# Battery_Charger.net
KiCad netlist of a schematic drawn in Altium Designer
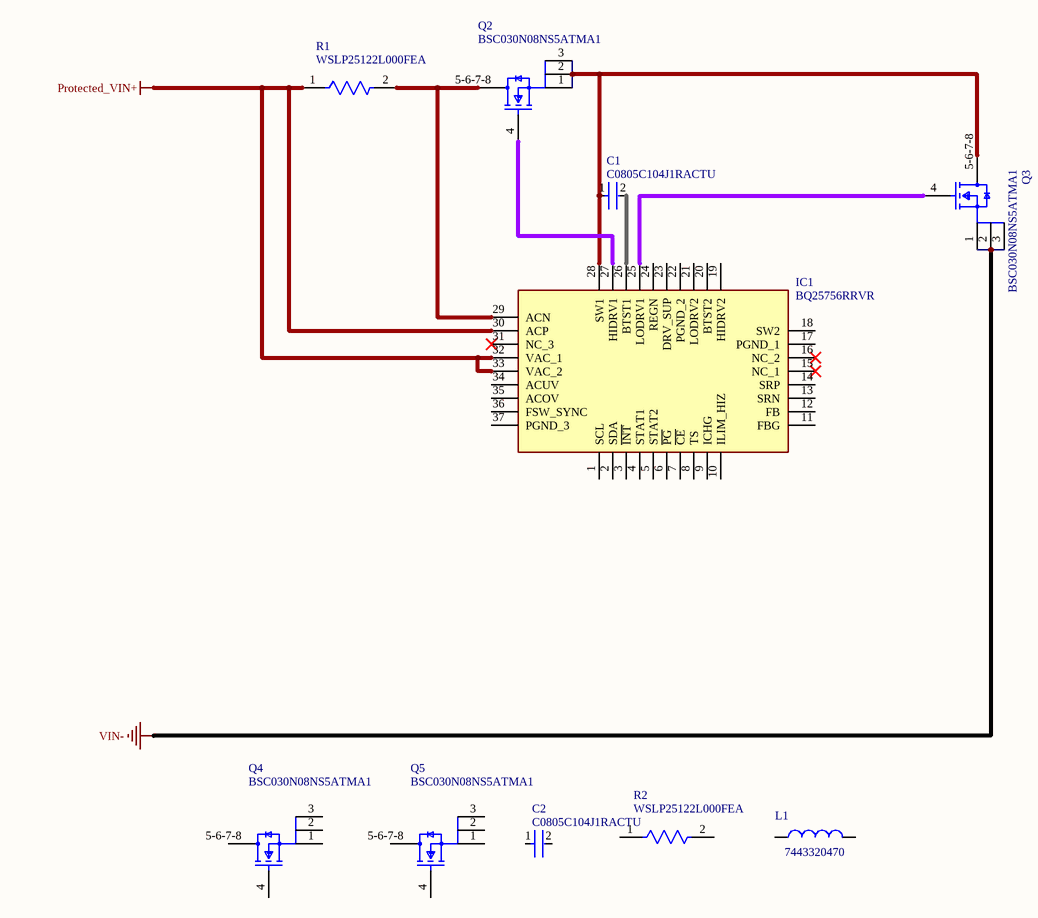
[diagram p0: Battery_Charger.SchDoc]

(export (version "E")
  (design (tool "Eeschema 10.0.6"))
  (components
    (comp (ref "C1")
      (value "C0805C104J1RACTU")
      (footprint "FP-C0805C-DN-MFG")
      (description "CAP CER 0.1UF 100V 5% X7R 0805")
      (fields
        (field (name "OCTOPART") "https://octopart.com/c0805c104j1ractu-kemet-10469001")
        (field (name "MANUFACTURER") "KEMET")
      )
      (libsource (lib "Altium Content Vault") (part "b4654b650e69147ec39a6b967a45e02"))
    )
    (comp (ref "C2")
      (value "C0805C104J1RACTU")
      (footprint "FP-C0805C-DN-MFG")
      (description "CAP CER 0.1UF 100V 5% X7R 0805")
      (fields
        (field (name "OCTOPART") "https://octopart.com/c0805c104j1ractu-kemet-10469001")
        (field (name "MANUFACTURER") "KEMET")
      )
      (libsource (lib "Altium Content Vault") (part "b4654b650e69147ec39a6b967a45e02"))
    )
    (comp (ref "IC1")
      (value "BQ25756RRVR")
      (footprint "BQ25756RRVR:QFN50P500X600X100-37N-D")
      (description "Integrated Circuit")
      (fields (field (name "MOUSER PART NUMBER") "595-BQ25756RRVR"))
      (libsource (lib "BQ25756RRVR") (part "BQ25756RRVR"))
    )
    (comp (ref "L1")
      (value "7443320470")
      (footprint "WE-HCC_1210")
      (description "We-hcc Series, Shielded Wire-wound SMD Inductor With Ferrite Core, 4.7 Uh")
      (libsource (lib "Altium Content Vault") (part "Inductor - 1"))
    )
    (comp (ref "Q2")
      (value "BSC030N08NS5ATMA1")
      (footprint "FP-PG-TDSON-8-MFG")
      (description "MOSFET N-CH 80V 100A 8TDSON")
      (fields
        (field (name "MANUFACTURER") "Infineon")
        (field (name "OCTOPART") "https://octopart.com/bsc030n08ns5atma1-infineon-52825708")
      )
      (libsource (lib "Altium Content Vault") (part "95ca5d46c4c8fe7d84c4fb5e2abfe3c"))
    )
    (comp (ref "Q3")
      (value "BSC030N08NS5ATMA1")
      (footprint "FP-PG-TDSON-8-MFG")
      (description "MOSFET N-CH 80V 100A 8TDSON")
      (fields
        (field (name "MANUFACTURER") "Infineon")
        (field (name "OCTOPART") "https://octopart.com/bsc030n08ns5atma1-infineon-52825708")
      )
      (libsource (lib "Altium Content Vault") (part "95ca5d46c4c8fe7d84c4fb5e2abfe3c"))
    )
    (comp (ref "Q4")
      (value "BSC030N08NS5ATMA1")
      (footprint "FP-PG-TDSON-8-MFG")
      (description "MOSFET N-CH 80V 100A 8TDSON")
      (fields
        (field (name "MANUFACTURER") "Infineon")
        (field (name "OCTOPART") "https://octopart.com/bsc030n08ns5atma1-infineon-52825708")
      )
      (libsource (lib "Altium Content Vault") (part "95ca5d46c4c8fe7d84c4fb5e2abfe3c"))
    )
    (comp (ref "Q5")
      (value "BSC030N08NS5ATMA1")
      (footprint "FP-PG-TDSON-8-MFG")
      (description "MOSFET N-CH 80V 100A 8TDSON")
      (fields
        (field (name "MANUFACTURER") "Infineon")
        (field (name "OCTOPART") "https://octopart.com/bsc030n08ns5atma1-infineon-52825708")
      )
      (libsource (lib "Altium Content Vault") (part "95ca5d46c4c8fe7d84c4fb5e2abfe3c"))
    )
    (comp (ref "R1")
      (value "WSLP25122L000FEA")
      (footprint "FP-WSLP2512-0R001-0R0049-MFG")
      (description "RES 0.002 OHM 1% 3W 2512")
      (fields (field (name "TOLERANCE") "1%"))
      (libsource (lib "Altium Content Vault") (part "1029c3af85768c4190bb7ad29bc67b5"))
    )
    (comp (ref "R2")
      (value "WSLP25122L000FEA")
      (footprint "FP-WSLP2512-0R001-0R0049-MFG")
      (description "RES 0.002 OHM 1% 3W 2512")
      (fields (field (name "TOLERANCE") "1%"))
      (libsource (lib "Altium Content Vault") (part "1029c3af85768c4190bb7ad29bc67b5"))
    )
  )
  (nets
    (net (code "1") (name "Net-(IC1-ACN)") (class "Default")
      (node (ref "IC1") (pin "29") (pinfunction "ACN_29") (pintype "passive"))
      (node (ref "Q2") (pin "5-6-7-8") (pinfunction "D_5-6-7-8") (pintype "passive"))
      (node (ref "R1") (pin "2") (pinfunction "2_2") (pintype "passive"))
    )
    (net (code "2") (name "Net-(IC1-BTST1)") (class "Default")
      (node (ref "C1") (pin "2") (pinfunction "2_2") (pintype "passive"))
      (node (ref "IC1") (pin "26") (pinfunction "BTST1_26") (pintype "passive"))
    )
    (net (code "3") (name "Net-(IC1-HIDRV1)") (class "Default")
      (node (ref "IC1") (pin "27") (pinfunction "HIDRV1_27") (pintype "passive"))
      (node (ref "Q2") (pin "4") (pinfunction "G_4") (pintype "passive"))
    )
    (net (code "4") (name "Net-(IC1-LODRV1)") (class "Default")
      (node (ref "IC1") (pin "25") (pinfunction "LODRV1_25") (pintype "passive"))
      (node (ref "Q3") (pin "4") (pinfunction "G_4") (pintype "passive"))
    )
    (net (code "5") (name "Net-(IC1-SW1)") (class "Default")
      (node (ref "C1") (pin "1") (pinfunction "1_1") (pintype "passive"))
      (node (ref "IC1") (pin "28") (pinfunction "SW1_28") (pintype "passive"))
      (node (ref "Q2") (pin "1") (pinfunction "S_1") (pintype "passive"))
      (node (ref "Q2") (pin "2") (pinfunction "S_2") (pintype "passive"))
      (node (ref "Q2") (pin "3") (pinfunction "S_3") (pintype "passive"))
      (node (ref "Q3") (pin "5-6-7-8") (pinfunction "D_5-6-7-8") (pintype "passive"))
    )
    (net (code "6") (name "Protected_VIN+") (class "Default")
      (node (ref "IC1") (pin "30") (pinfunction "ACP_30") (pintype "passive"))
      (node (ref "IC1") (pin "32") (pinfunction "VAC_1_32") (pintype "passive"))
      (node (ref "IC1") (pin "33") (pinfunction "VAC_2_33") (pintype "passive"))
      (node (ref "R1") (pin "1") (pinfunction "1_1") (pintype "passive"))
    )
    (net (code "7") (name "VIN-") (class "Default")
      (node (ref "Q3") (pin "1") (pinfunction "S_1") (pintype "passive"))
      (node (ref "Q3") (pin "2") (pinfunction "S_2") (pintype "passive"))
      (node (ref "Q3") (pin "3") (pinfunction "S_3") (pintype "passive"))
    )
    (net (code "8") (name "unconnected-(C2-Pad1)") (class "Default")
      (node (ref "C2") (pin "1") (pinfunction "1_1") (pintype "passive"))
    )
    (net (code "9") (name "unconnected-(C2-Pad2)") (class "Default")
      (node (ref "C2") (pin "2") (pinfunction "2_2") (pintype "passive"))
    )
    (net (code "10") (name "unconnected-(IC1-ACOV-Pad35)") (class "Default")
      (node (ref "IC1") (pin "35") (pinfunction "ACOV_35") (pintype "passive"))
    )
    (net (code "11") (name "unconnected-(IC1-ACUV-Pad34)") (class "Default")
      (node (ref "IC1") (pin "34") (pinfunction "ACUV_34") (pintype "passive"))
    )
    (net (code "12") (name "unconnected-(IC1-BTST2-Pad20)") (class "Default")
      (node (ref "IC1") (pin "20") (pinfunction "BTST2_20") (pintype "passive"))
    )
    (net (code "13") (name "unconnected-(IC1-DRV_SUP-Pad23)") (class "Default")
      (node (ref "IC1") (pin "23") (pinfunction "DRV_SUP_23") (pintype "passive"))
    )
    (net (code "14") (name "unconnected-(IC1-FB-Pad12)") (class "Default")
      (node (ref "IC1") (pin "12") (pinfunction "FB_12") (pintype "passive"))
    )
    (net (code "15") (name "unconnected-(IC1-FBG-Pad11)") (class "Default")
      (node (ref "IC1") (pin "11") (pinfunction "FBG_11") (pintype "passive"))
    )
    (net (code "16") (name "unconnected-(IC1-FSW_SYNC-Pad36)") (class "Default")
      (node (ref "IC1") (pin "36") (pinfunction "FSW_SYNC_36") (pintype "passive"))
    )
    (net (code "17") (name "unconnected-(IC1-HIDRV2-Pad19)") (class "Default")
      (node (ref "IC1") (pin "19") (pinfunction "HIDRV2_19") (pintype "passive"))
    )
    (net (code "18") (name "unconnected-(IC1-ICHG-Pad9)") (class "Default")
      (node (ref "IC1") (pin "9") (pinfunction "ICHG_9") (pintype "passive"))
    )
    (net (code "19") (name "unconnected-(IC1-ILIM_HIZ-Pad10)") (class "Default")
      (node (ref "IC1") (pin "10") (pinfunction "ILIM_HIZ_10") (pintype "passive"))
    )
    (net (code "20") (name "unconnected-(IC1-LODRV2-Pad21)") (class "Default")
      (node (ref "IC1") (pin "21") (pinfunction "LODRV2_21") (pintype "passive"))
    )
    (net (code "21") (name "unconnected-(IC1-NC_1-Pad15)") (class "Default")
      (node (ref "IC1") (pin "15") (pinfunction "NC_1_15") (pintype "passive+no_connect"))
    )
    (net (code "22") (name "unconnected-(IC1-NC_2-Pad16)") (class "Default")
      (node (ref "IC1") (pin "16") (pinfunction "NC_2_16") (pintype "passive+no_connect"))
    )
    (net (code "23") (name "unconnected-(IC1-NC_3-Pad31)") (class "Default")
      (node (ref "IC1") (pin "31") (pinfunction "NC_3_31") (pintype "passive+no_connect"))
    )
    (net (code "24") (name "unconnected-(IC1-PGND_1-Pad17)") (class "Default")
      (node (ref "IC1") (pin "17") (pinfunction "PGND_1_17") (pintype "passive"))
    )
    (net (code "25") (name "unconnected-(IC1-PGND_2-Pad22)") (class "Default")
      (node (ref "IC1") (pin "22") (pinfunction "PGND_2_22") (pintype "passive"))
    )
    (net (code "26") (name "unconnected-(IC1-PGND_3-Pad37)") (class "Default")
      (node (ref "IC1") (pin "37") (pinfunction "PGND_3_37") (pintype "passive"))
    )
    (net (code "27") (name "unconnected-(IC1-REGN-Pad24)") (class "Default")
      (node (ref "IC1") (pin "24") (pinfunction "REGN_24") (pintype "passive"))
    )
    (net (code "28") (name "unconnected-(IC1-SCL-Pad1)") (class "Default")
      (node (ref "IC1") (pin "1") (pinfunction "SCL_1") (pintype "passive"))
    )
    (net (code "29") (name "unconnected-(IC1-SDA-Pad2)") (class "Default")
      (node (ref "IC1") (pin "2") (pinfunction "SDA_2") (pintype "passive"))
    )
    (net (code "30") (name "unconnected-(IC1-SRN-Pad13)") (class "Default")
      (node (ref "IC1") (pin "13") (pinfunction "SRN_13") (pintype "passive"))
    )
    (net (code "31") (name "unconnected-(IC1-SRP-Pad14)") (class "Default")
      (node (ref "IC1") (pin "14") (pinfunction "SRP_14") (pintype "passive"))
    )
    (net (code "32") (name "unconnected-(IC1-STAT1-Pad4)") (class "Default")
      (node (ref "IC1") (pin "4") (pinfunction "STAT1_4") (pintype "passive"))
    )
    (net (code "33") (name "unconnected-(IC1-STAT2-Pad5)") (class "Default")
      (node (ref "IC1") (pin "5") (pinfunction "STAT2_5") (pintype "passive"))
    )
    (net (code "34") (name "unconnected-(IC1-SW2-Pad18)") (class "Default")
      (node (ref "IC1") (pin "18") (pinfunction "SW2_18") (pintype "passive"))
    )
    (net (code "35") (name "unconnected-(IC1-TS-Pad8)") (class "Default")
      (node (ref "IC1") (pin "8") (pinfunction "TS_8") (pintype "passive"))
    )
    (net (code "36") (name "unconnected-(IC1-~{CE}-Pad7)") (class "Default")
      (node (ref "IC1") (pin "7") (pinfunction "~{CE}_7") (pintype "passive"))
    )
    (net (code "37") (name "unconnected-(IC1-~{INT}-Pad3)") (class "Default")
      (node (ref "IC1") (pin "3") (pinfunction "~{INT}_3") (pintype "passive"))
    )
    (net (code "38") (name "unconnected-(IC1-~{PG}-Pad6)") (class "Default")
      (node (ref "IC1") (pin "6") (pinfunction "~{PG}_6") (pintype "passive"))
    )
    (net (code "39") (name "unconnected-(L1-Pad1)") (class "Default")
      (node (ref "L1") (pin "1") (pinfunction "1_1") (pintype "passive"))
    )
    (net (code "40") (name "unconnected-(L1-Pad2)") (class "Default")
      (node (ref "L1") (pin "2") (pinfunction "2_2") (pintype "passive"))
    )
    (net (code "41") (name "unconnected-(Q4-D-Pad5-6-7-8)") (class "Default")
      (node (ref "Q4") (pin "5-6-7-8") (pinfunction "D_5-6-7-8") (pintype "passive"))
    )
    (net (code "42") (name "unconnected-(Q4-G-Pad4)") (class "Default")
      (node (ref "Q4") (pin "4") (pinfunction "G_4") (pintype "passive"))
    )
    (net (code "43") (name "unconnected-(Q4-S-Pad1)") (class "Default")
      (node (ref "Q4") (pin "1") (pinfunction "S_1") (pintype "passive"))
    )
    (net (code "44") (name "unconnected-(Q4-S-Pad2)") (class "Default")
      (node (ref "Q4") (pin "2") (pinfunction "S_2") (pintype "passive"))
    )
    (net (code "45") (name "unconnected-(Q4-S-Pad3)") (class "Default")
      (node (ref "Q4") (pin "3") (pinfunction "S_3") (pintype "passive"))
    )
    (net (code "46") (name "unconnected-(Q5-D-Pad5-6-7-8)") (class "Default")
      (node (ref "Q5") (pin "5-6-7-8") (pinfunction "D_5-6-7-8") (pintype "passive"))
    )
    (net (code "47") (name "unconnected-(Q5-G-Pad4)") (class "Default")
      (node (ref "Q5") (pin "4") (pinfunction "G_4") (pintype "passive"))
    )
    (net (code "48") (name "unconnected-(Q5-S-Pad1)") (class "Default")
      (node (ref "Q5") (pin "1") (pinfunction "S_1") (pintype "passive"))
    )
    (net (code "49") (name "unconnected-(Q5-S-Pad2)") (class "Default")
      (node (ref "Q5") (pin "2") (pinfunction "S_2") (pintype "passive"))
    )
    (net (code "50") (name "unconnected-(Q5-S-Pad3)") (class "Default")
      (node (ref "Q5") (pin "3") (pinfunction "S_3") (pintype "passive"))
    )
    (net (code "51") (name "unconnected-(R2-Pad1)") (class "Default")
      (node (ref "R2") (pin "1") (pinfunction "1_1") (pintype "passive"))
    )
    (net (code "52") (name "unconnected-(R2-Pad2)") (class "Default")
      (node (ref "R2") (pin "2") (pinfunction "2_2") (pintype "passive"))
    )
  )
)
